# Power.net
KiCad netlist of a schematic drawn in Altium Designer
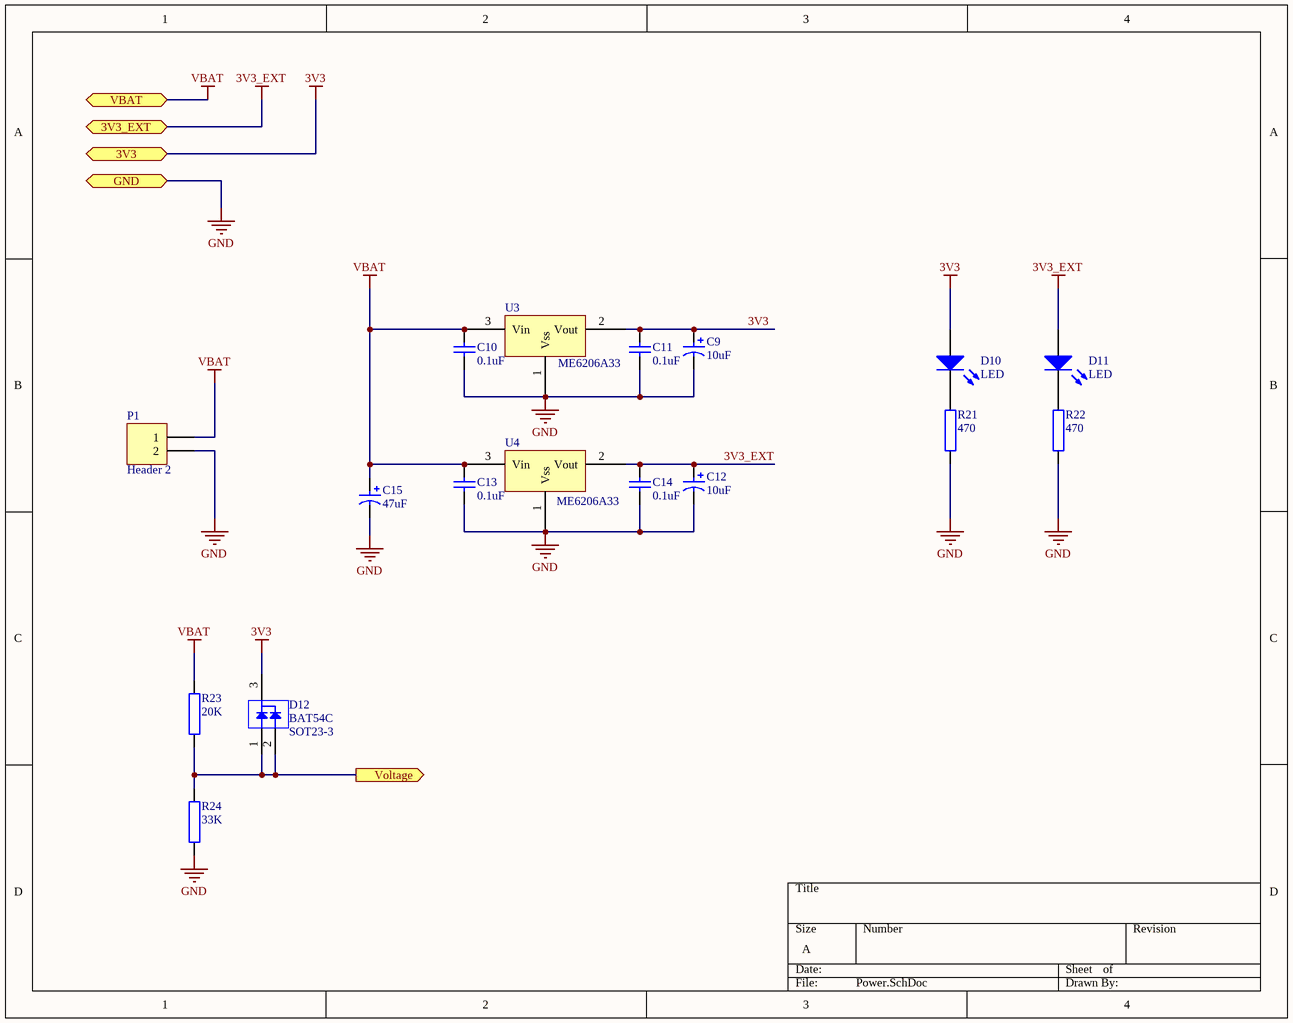
[diagram p0: Power.SchDoc]

(export (version "E")
  (design (tool "Eeschema 10.0.6"))
  (components
    (comp (ref "C9")
      (value "10uF")
      (footprint "Cap_Ta_A_Case")
      (description "Polarized Capacitor (Surface Mount)")
      (fields (field (name "PUBLISHER") "Altium Limited"))
      (libsource (lib "Quadcopter") (part "Cap Tantalum"))
    )
    (comp (ref "C10")
      (value "0.1uF")
      (footprint "C0603")
      (description "Capacitor (Semiconductor SIM Model)")
      (fields (field (name "PUBLISHER") "Altium Limited"))
      (libsource (lib "Quadcopter") (part "Cap"))
    )
    (comp (ref "C11")
      (value "0.1uF")
      (footprint "C0603")
      (description "Capacitor (Semiconductor SIM Model)")
      (fields (field (name "PUBLISHER") "Altium Limited"))
      (libsource (lib "Quadcopter") (part "Cap"))
    )
    (comp (ref "C12")
      (value "10uF")
      (footprint "Cap_Ta_A_Case")
      (description "Polarized Capacitor (Surface Mount)")
      (fields (field (name "PUBLISHER") "Altium Limited"))
      (libsource (lib "Quadcopter") (part "Cap Tantalum"))
    )
    (comp (ref "C13")
      (value "0.1uF")
      (footprint "C0603")
      (description "Capacitor (Semiconductor SIM Model)")
      (fields (field (name "PUBLISHER") "Altium Limited"))
      (libsource (lib "Quadcopter") (part "Cap"))
    )
    (comp (ref "C14")
      (value "0.1uF")
      (footprint "C0603")
      (description "Capacitor (Semiconductor SIM Model)")
      (fields (field (name "PUBLISHER") "Altium Limited"))
      (libsource (lib "Quadcopter") (part "Cap"))
    )
    (comp (ref "C15")
      (value "47uF")
      (footprint "Cap_Ta_B_Case")
      (description "Polarized Capacitor (Surface Mount)")
      (fields (field (name "PUBLISHER") "Altium Limited"))
      (libsource (lib "Quadcopter") (part "Cap Tantalum"))
    )
    (comp (ref "D10")
      (value "LED")
      (footprint "LED_0603")
      (description "Typical INFRARED GaAs LED")
      (fields (field (name "PUBLISHER") "Altium Limited"))
      (libsource (lib "Quadcopter") (part "LED"))
    )
    (comp (ref "D11")
      (value "LED")
      (footprint "LED_0603")
      (description "Typical INFRARED GaAs LED")
      (fields (field (name "PUBLISHER") "Altium Limited"))
      (libsource (lib "Quadcopter") (part "LED"))
    )
    (comp (ref "D12") (value "BAT54C") (footprint "SOT23-3") (libsource (lib "Quadcopter") (part "BAT54C")))
    (comp (ref "P1")
      (value "Header 2")
      (footprint "HDR1X2")
      (description "Header, 2-Pin")
      (fields (field (name "PUBLISHER") "Altium Limited"))
      (libsource (lib "Miscellaneous Connectors") (part "Header 2"))
    )
    (comp (ref "R21")
      (value "470")
      (footprint "R0603")
      (description "Resistor")
      (fields (field (name "PUBLISHER") "Altium Limited"))
      (libsource (lib "Quadcopter") (part "Res3"))
    )
    (comp (ref "R22")
      (value "470")
      (footprint "R0603")
      (description "Resistor")
      (fields (field (name "PUBLISHER") "Altium Limited"))
      (libsource (lib "Quadcopter") (part "Res3"))
    )
    (comp (ref "R23")
      (value "20K")
      (footprint "r0603")
      (description "Resistor")
      (fields (field (name "PUBLISHER") "Altium Limited"))
      (libsource (lib "Quadcopter") (part "Res3"))
    )
    (comp (ref "R24")
      (value "33K")
      (footprint "r0603")
      (description "Resistor")
      (fields (field (name "PUBLISHER") "Altium Limited"))
      (libsource (lib "Quadcopter") (part "Res3"))
    )
    (comp (ref "U3")
      (value "ME6206A33")
      (footprint "SOT23-3")
      (description "ME6206A33, SOT23")
      (libsource (lib "Quadcopter") (part "ME6206"))
    )
    (comp (ref "U4")
      (value "ME6206A33")
      (footprint "SOT23-3")
      (description "ME6206A33, SOT23")
      (libsource (lib "Quadcopter") (part "ME6206"))
    )
  )
  (nets
    (net (code "1") (name "/Voltage") (class "Default")
      (node (ref "D12") (pin "1") (pinfunction "1_1") (pintype "passive"))
      (node (ref "D12") (pin "2") (pinfunction "2_2") (pintype "passive"))
      (node (ref "R23") (pin "1") (pinfunction "1_1") (pintype "passive"))
      (node (ref "R24") (pin "2") (pinfunction "2_2") (pintype "passive"))
    )
    (net (code "2") (name "3V3") (class "Default")
      (node (ref "C11") (pin "1") (pinfunction "1_1") (pintype "passive"))
      (node (ref "C9") (pin "1") (pinfunction "1_1") (pintype "passive"))
      (node (ref "D10") (pin "1") (pinfunction "A_1") (pintype "passive"))
      (node (ref "D12") (pin "3") (pinfunction "3_3") (pintype "passive"))
      (node (ref "U3") (pin "2") (pinfunction "Vout_2") (pintype "passive"))
    )
    (net (code "3") (name "3V3_EXT") (class "Default")
      (node (ref "C12") (pin "1") (pinfunction "1_1") (pintype "passive"))
      (node (ref "C14") (pin "1") (pinfunction "1_1") (pintype "passive"))
      (node (ref "D11") (pin "1") (pinfunction "A_1") (pintype "passive"))
      (node (ref "U4") (pin "2") (pinfunction "Vout_2") (pintype "passive"))
    )
    (net (code "4") (name "GND") (class "Default")
      (node (ref "C10") (pin "2") (pinfunction "2_2") (pintype "passive"))
      (node (ref "C11") (pin "2") (pinfunction "2_2") (pintype "passive"))
      (node (ref "C12") (pin "2") (pinfunction "2_2") (pintype "passive"))
      (node (ref "C13") (pin "2") (pinfunction "2_2") (pintype "passive"))
      (node (ref "C14") (pin "2") (pinfunction "2_2") (pintype "passive"))
      (node (ref "C15") (pin "2") (pinfunction "2_2") (pintype "passive"))
      (node (ref "C9") (pin "2") (pinfunction "2_2") (pintype "passive"))
      (node (ref "P1") (pin "2") (pinfunction "2_2") (pintype "passive"))
      (node (ref "R21") (pin "1") (pinfunction "1_1") (pintype "passive"))
      (node (ref "R22") (pin "1") (pinfunction "1_1") (pintype "passive"))
      (node (ref "R24") (pin "1") (pinfunction "1_1") (pintype "passive"))
      (node (ref "U3") (pin "1") (pinfunction "Vss_1") (pintype "passive"))
      (node (ref "U4") (pin "1") (pinfunction "Vss_1") (pintype "passive"))
    )
    (net (code "5") (name "Net-(D10-K)") (class "Default")
      (node (ref "D10") (pin "2") (pinfunction "K_2") (pintype "passive"))
      (node (ref "R21") (pin "2") (pinfunction "2_2") (pintype "passive"))
    )
    (net (code "6") (name "Net-(D11-K)") (class "Default")
      (node (ref "D11") (pin "2") (pinfunction "K_2") (pintype "passive"))
      (node (ref "R22") (pin "2") (pinfunction "2_2") (pintype "passive"))
    )
    (net (code "7") (name "VBAT") (class "Default")
      (node (ref "C10") (pin "1") (pinfunction "1_1") (pintype "passive"))
      (node (ref "C13") (pin "1") (pinfunction "1_1") (pintype "passive"))
      (node (ref "C15") (pin "1") (pinfunction "1_1") (pintype "passive"))
      (node (ref "P1") (pin "1") (pinfunction "1_1") (pintype "passive"))
      (node (ref "R23") (pin "2") (pinfunction "2_2") (pintype "passive"))
      (node (ref "U3") (pin "3") (pinfunction "Vin_3") (pintype "passive"))
      (node (ref "U4") (pin "3") (pinfunction "Vin_3") (pintype "passive"))
    )
  )
)
